# payload-schematic.net
KiCad netlist of a schematic drawn in EAGLE
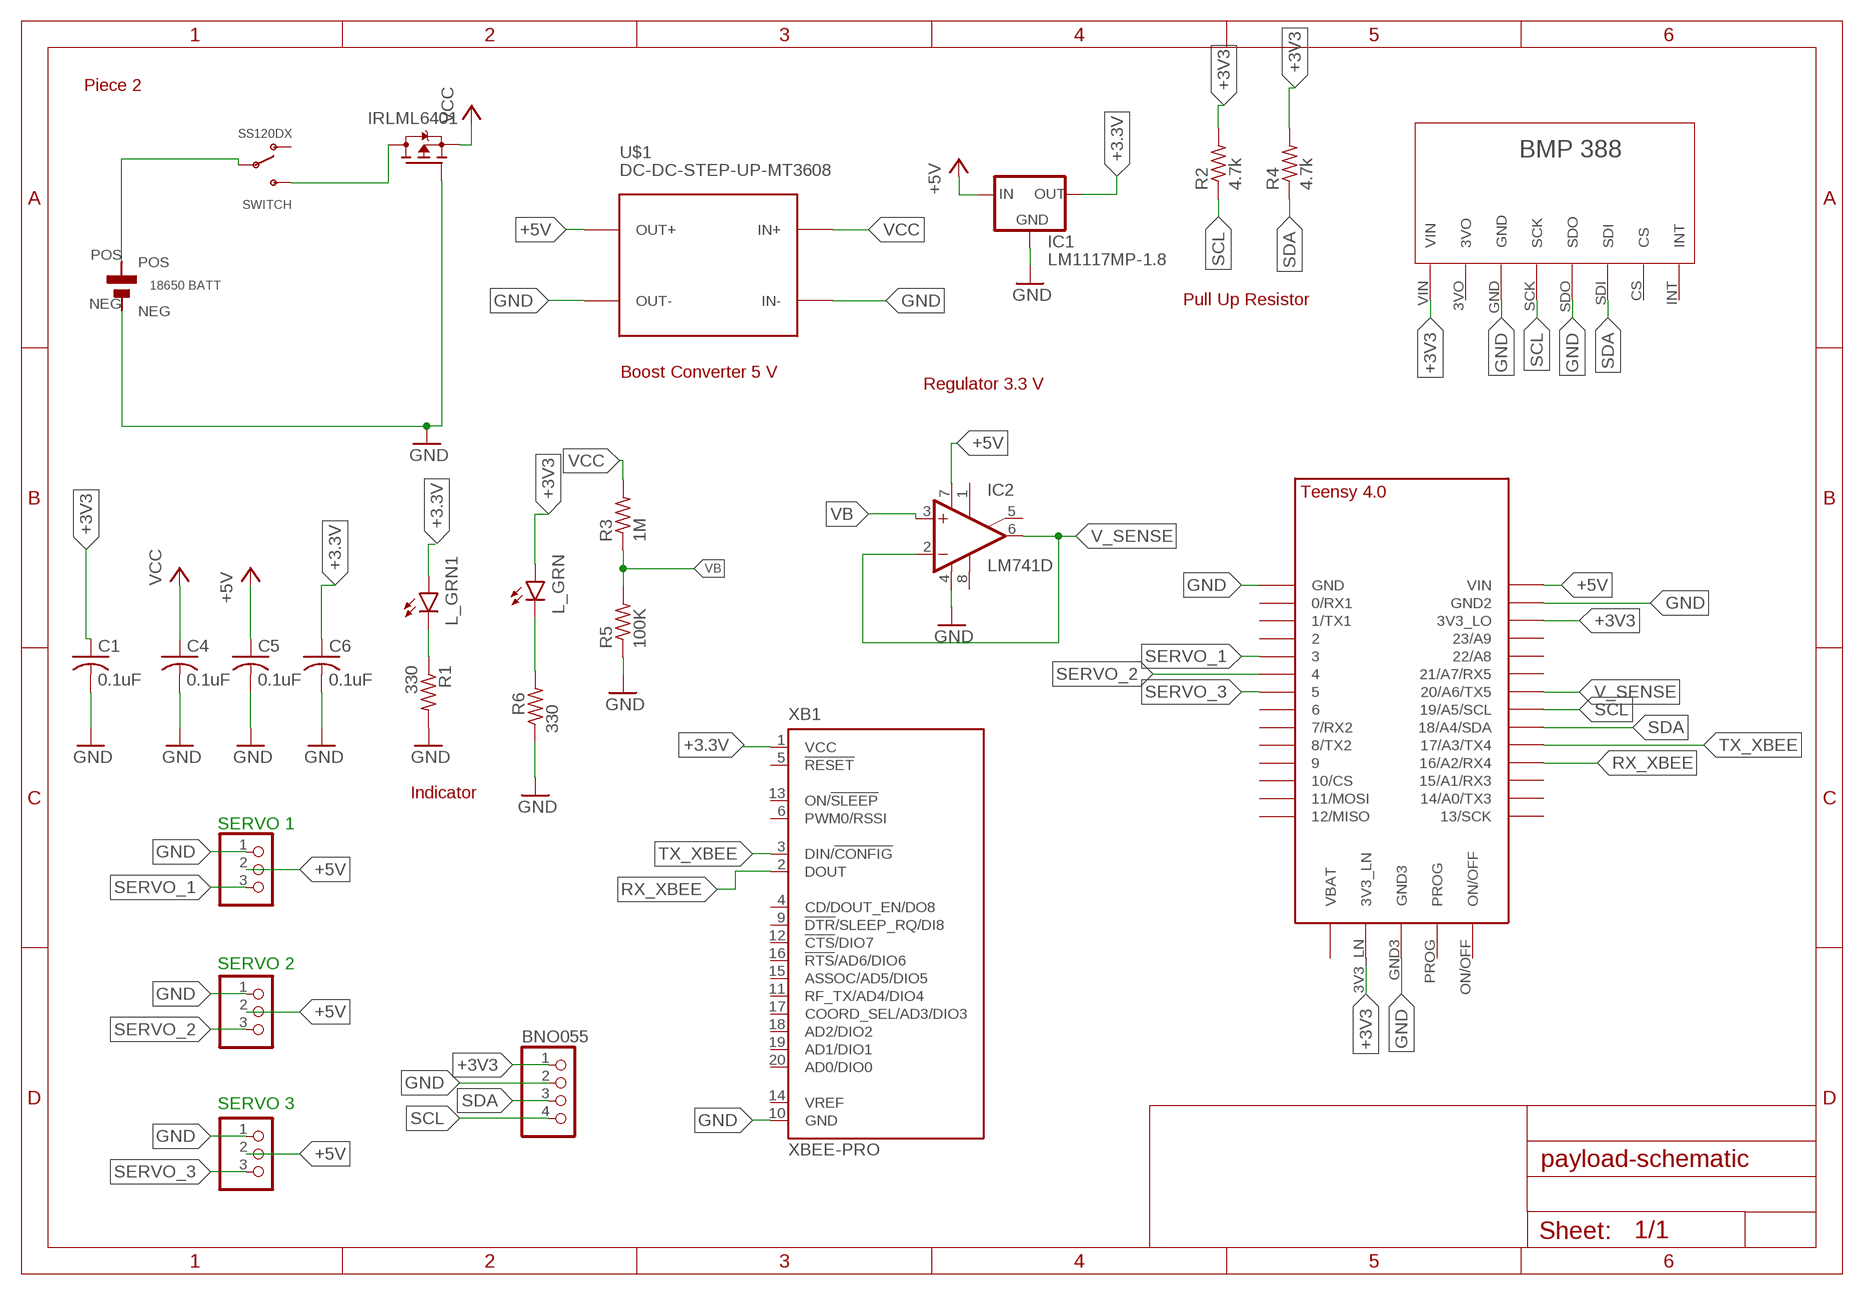
[diagram p0: schematic, sheet 1]

(export (version "E")
  (design (tool "Eeschema 10.0.6"))
  (components
    (comp (ref "BNO055")
      (value "PINHD-1X4")
      (footprint "eagle-import:1X04")
      (libsource (lib "eagle-import") (part "PINHD-1X4"))
    )
    (comp (ref "C1")
      (value "0.1uF")
      (footprint "eagle-import:C0805")
      (libsource (lib "eagle-import") (part "C-USC0805"))
    )
    (comp (ref "C4")
      (value "0.1uF")
      (footprint "eagle-import:C0805")
      (libsource (lib "eagle-import") (part "C-USC0805"))
    )
    (comp (ref "C5")
      (value "0.1uF")
      (footprint "eagle-import:C0805")
      (libsource (lib "eagle-import") (part "C-USC0805"))
    )
    (comp (ref "C6")
      (value "0.1uF")
      (footprint "eagle-import:C0805")
      (libsource (lib "eagle-import") (part "C-USC0805"))
    )
    (comp (ref "IC1")
      (value "LM1117MP-1.8")
      (footprint "eagle-import:SOT223")
      (fields (field (name "MF") "Texas Instruments"))
      (libsource (lib "eagle-import") (part "LM1117?-MP1.8"))
    )
    (comp (ref "IC2")
      (value "LM741D")
      (footprint "eagle-import:SO08")
      (libsource (lib "eagle-import") (part "741DLM"))
    )
    (comp (ref "IRLML6401")
      (value "MOSFET-PWIDE")
      (footprint "eagle-import:SOT23-WIDE")
      (libsource (lib "eagle-import") (part "MOSFET-PWIDE"))
    )
    (comp (ref "L_GRN")
      (value "LED1206")
      (footprint "eagle-import:LED-1206")
      (libsource (lib "eagle-import") (part "LED1206"))
    )
    (comp (ref "L_GRN1")
      (value "LED1206")
      (footprint "eagle-import:LED-1206")
      (libsource (lib "eagle-import") (part "LED1206"))
    )
    (comp (ref "R1")
      (value "330")
      (footprint "eagle-import:M0805")
      (libsource (lib "eagle-import") (part "R-US_M0805"))
    )
    (comp (ref "R2")
      (value "4.7k")
      (footprint "eagle-import:M0805")
      (libsource (lib "eagle-import") (part "R-US_M0805"))
    )
    (comp (ref "R3")
      (value "1M")
      (footprint "eagle-import:M1206")
      (libsource (lib "eagle-import") (part "R-US_M1206"))
    )
    (comp (ref "R4")
      (value "4.7k")
      (footprint "eagle-import:M0805")
      (libsource (lib "eagle-import") (part "R-US_M0805"))
    )
    (comp (ref "R5")
      (value "100K")
      (footprint "eagle-import:M1206")
      (libsource (lib "eagle-import") (part "R-US_M1206"))
    )
    (comp (ref "R6")
      (value "330")
      (footprint "eagle-import:M0805")
      (libsource (lib "eagle-import") (part "R-US_M0805"))
    )
    (comp (ref "SERVO1")
      (value "PINHD-1X3")
      (footprint "eagle-import:1X03")
      (libsource (lib "eagle-import") (part "PINHD-1X3"))
    )
    (comp (ref "SERVO2")
      (value "PINHD-1X3")
      (footprint "eagle-import:1X03")
      (libsource (lib "eagle-import") (part "PINHD-1X3"))
    )
    (comp (ref "SERVO3")
      (value "PINHD-1X3")
      (footprint "eagle-import:1X03")
      (libsource (lib "eagle-import") (part "PINHD-1X3"))
    )
    (comp (ref "SWITCH")
      (value "SS120DX")
      (footprint "eagle-import:SS12D0X")
      (libsource (lib "eagle-import") (part "SS120DX"))
    )
    (comp (ref "U$1")
      (value "DC-DC-STEP-UP-MT3608")
      (footprint "eagle-import:DC-DC-STEP-UP-MT3608")
      (libsource (lib "eagle-import") (part "DC-DC-STEP-UP-MT3608"))
    )
    (comp (ref "U$3")
      (value "BMP388")
      (footprint "eagle-import:BMP388")
      (libsource (lib "eagle-import") (part "BMP388"))
    )
    (comp (ref "U$4")
      (value "18650")
      (footprint "eagle-import:18650")
      (libsource (lib "eagle-import") (part "18650"))
    )
    (comp (ref "U$6")
      (value "TEENSY_4.0")
      (footprint "eagle-import:TEENSY_4.0")
      (libsource (lib "eagle-import") (part "TEENSY_4.0"))
    )
    (comp (ref "XB1")
      (value "XBEE-PRO")
      (footprint "eagle-import:XBEE-PRO")
      (fields (field (name "MPN") "XBP24-AWI-001"))
      (libsource (lib "eagle-import") (part "XBEE-PRO"))
    )
  )
  (nets
    (net (code "1") (name "+3.3V") (class "Default")
      (node (ref "C6") (pin "1") (pinfunction "1_1") (pintype "passive"))
      (node (ref "IC1") (pin "2") (pinfunction "OUT_2") (pintype "passive"))
      (node (ref "IC1") (pin "4") (pinfunction "OUT_4") (pintype "passive"))
      (node (ref "L_GRN1") (pin "A") (pinfunction "A_A") (pintype "passive"))
      (node (ref "XB1") (pin "1") (pinfunction "VCC_1") (pintype "power_in"))
    )
    (net (code "2") (name "+3V3") (class "Default")
      (node (ref "BNO055") (pin "1") (pinfunction "1_1") (pintype "passive"))
      (node (ref "C1") (pin "1") (pinfunction "1_1") (pintype "passive"))
      (node (ref "L_GRN") (pin "A") (pinfunction "A_A") (pintype "passive"))
      (node (ref "R2") (pin "2") (pinfunction "2_2") (pintype "passive"))
      (node (ref "R4") (pin "2") (pinfunction "2_2") (pintype "passive"))
      (node (ref "U$3") (pin "VIN") (pinfunction "VIN_VIN") (pintype "bidirectional"))
      (node (ref "U$6") (pin "3V3_LN") (pinfunction "3V3_LN_3V3_LN") (pintype "bidirectional"))
      (node (ref "U$6") (pin "3V3_LO") (pinfunction "3V3_LO_3V3_LO") (pintype "bidirectional"))
    )
    (net (code "3") (name "+5V") (class "Default")
      (node (ref "C5") (pin "1") (pinfunction "1_1") (pintype "passive"))
      (node (ref "IC1") (pin "3") (pinfunction "IN_3") (pintype "input"))
      (node (ref "IC2") (pin "7") (pinfunction "V+_7") (pintype "power_in"))
      (node (ref "SERVO1") (pin "2") (pinfunction "2_2") (pintype "passive"))
      (node (ref "SERVO2") (pin "2") (pinfunction "2_2") (pintype "passive"))
      (node (ref "SERVO3") (pin "2") (pinfunction "2_2") (pintype "passive"))
      (node (ref "U$1") (pin "OUT+") (pinfunction "OUT+_OUT+") (pintype "bidirectional"))
      (node (ref "U$6") (pin "VIN") (pinfunction "VIN_VIN") (pintype "bidirectional"))
    )
    (net (code "4") (name "GND") (class "Default")
      (node (ref "BNO055") (pin "2") (pinfunction "2_2") (pintype "passive"))
      (node (ref "C1") (pin "2") (pinfunction "2_2") (pintype "passive"))
      (node (ref "C4") (pin "2") (pinfunction "2_2") (pintype "passive"))
      (node (ref "C5") (pin "2") (pinfunction "2_2") (pintype "passive"))
      (node (ref "C6") (pin "2") (pinfunction "2_2") (pintype "passive"))
      (node (ref "IC1") (pin "1") (pinfunction "GND_1") (pintype "input"))
      (node (ref "IC2") (pin "4") (pinfunction "V-_4") (pintype "power_in"))
      (node (ref "IRLML6401") (pin "1") (pinfunction "G_1") (pintype "passive"))
      (node (ref "R1") (pin "2") (pinfunction "2_2") (pintype "passive"))
      (node (ref "R5") (pin "1") (pinfunction "1_1") (pintype "passive"))
      (node (ref "R6") (pin "1") (pinfunction "1_1") (pintype "passive"))
      (node (ref "SERVO1") (pin "1") (pinfunction "1_1") (pintype "passive"))
      (node (ref "SERVO2") (pin "1") (pinfunction "1_1") (pintype "passive"))
      (node (ref "SERVO3") (pin "1") (pinfunction "1_1") (pintype "passive"))
      (node (ref "U$1") (pin "IN-") (pinfunction "IN-_IN-") (pintype "bidirectional"))
      (node (ref "U$1") (pin "OUT-") (pinfunction "OUT-_OUT-") (pintype "bidirectional"))
      (node (ref "U$3") (pin "GND") (pinfunction "GND_GND") (pintype "bidirectional"))
      (node (ref "U$3") (pin "SDO") (pinfunction "SDO_SDO") (pintype "bidirectional"))
      (node (ref "U$4") (pin "NEG") (pinfunction "NEG_NEG") (pintype "bidirectional"))
      (node (ref "U$6") (pin "GND") (pinfunction "GND_GND") (pintype "bidirectional"))
      (node (ref "U$6") (pin "GND2") (pinfunction "GND2_GND2") (pintype "bidirectional"))
      (node (ref "U$6") (pin "GND3") (pinfunction "GND3_GND3") (pintype "bidirectional"))
      (node (ref "XB1") (pin "10") (pinfunction "GND_10") (pintype "power_in"))
    )
    (net (code "5") (name "Net-(IRLML6401-D)") (class "Default")
      (node (ref "IRLML6401") (pin "3") (pinfunction "D_3") (pintype "passive"))
      (node (ref "SWITCH") (pin "3") (pinfunction "3_3") (pintype "passive"))
    )
    (net (code "6") (name "Net-(L_GRN-PadC)") (class "Default")
      (node (ref "L_GRN") (pin "C") (pinfunction "C_C") (pintype "passive"))
      (node (ref "R6") (pin "2") (pinfunction "2_2") (pintype "passive"))
    )
    (net (code "7") (name "Net-(L_GRN1-PadC)") (class "Default")
      (node (ref "L_GRN1") (pin "C") (pinfunction "C_C") (pintype "passive"))
      (node (ref "R1") (pin "1") (pinfunction "1_1") (pintype "passive"))
    )
    (net (code "8") (name "Net-(SWITCH-Pad2)") (class "Default")
      (node (ref "SWITCH") (pin "2") (pinfunction "2_2") (pintype "passive"))
      (node (ref "U$4") (pin "POS") (pinfunction "POS_POS") (pintype "bidirectional"))
    )
    (net (code "9") (name "RX_XBEE") (class "Default")
      (node (ref "U$6") (pin "16/A2") (pinfunction "16/A2/RX4_16/A2") (pintype "bidirectional"))
      (node (ref "XB1") (pin "2") (pinfunction "DOUT_2") (pintype "output"))
    )
    (net (code "10") (name "SCL") (class "Default")
      (node (ref "BNO055") (pin "4") (pinfunction "4_4") (pintype "passive"))
      (node (ref "R2") (pin "1") (pinfunction "1_1") (pintype "passive"))
      (node (ref "U$3") (pin "SCK") (pinfunction "SCK_SCK") (pintype "bidirectional"))
      (node (ref "U$6") (pin "19/A5/SCL") (pinfunction "19/A5/SCL_19/A5/SCL") (pintype "bidirectional"))
    )
    (net (code "11") (name "SDA") (class "Default")
      (node (ref "BNO055") (pin "3") (pinfunction "3_3") (pintype "passive"))
      (node (ref "R4") (pin "1") (pinfunction "1_1") (pintype "passive"))
      (node (ref "U$3") (pin "SDI") (pinfunction "SDI_SDI") (pintype "bidirectional"))
      (node (ref "U$6") (pin "18/A4/SDA") (pinfunction "18/A4/SDA_18/A4/SDA") (pintype "bidirectional"))
    )
    (net (code "12") (name "SERVO_1") (class "Default")
      (node (ref "SERVO1") (pin "3") (pinfunction "3_3") (pintype "passive"))
      (node (ref "U$6") (pin "3/CANTX") (pinfunction "3_3/CANTX") (pintype "bidirectional"))
    )
    (net (code "13") (name "SERVO_2") (class "Default")
      (node (ref "SERVO2") (pin "3") (pinfunction "3_3") (pintype "passive"))
      (node (ref "U$6") (pin "4/CANRX") (pinfunction "4_4/CANRX") (pintype "bidirectional"))
    )
    (net (code "14") (name "SERVO_3") (class "Default")
      (node (ref "SERVO3") (pin "3") (pinfunction "3_3") (pintype "passive"))
      (node (ref "U$6") (pin "5") (pinfunction "5_5") (pintype "bidirectional"))
    )
    (net (code "15") (name "TX_XBEE") (class "Default")
      (node (ref "U$6") (pin "17/A3") (pinfunction "17/A3/TX4_17/A3") (pintype "bidirectional"))
      (node (ref "XB1") (pin "3") (pinfunction "DIN/~{CONFIG}_3") (pintype "input"))
    )
    (net (code "16") (name "VB") (class "Default")
      (node (ref "IC2") (pin "3") (pinfunction "+IN_3") (pintype "input"))
      (node (ref "R3") (pin "1") (pinfunction "1_1") (pintype "passive"))
      (node (ref "R5") (pin "2") (pinfunction "2_2") (pintype "passive"))
    )
    (net (code "17") (name "VCC") (class "Default")
      (node (ref "C4") (pin "1") (pinfunction "1_1") (pintype "passive"))
      (node (ref "IRLML6401") (pin "2") (pinfunction "S_2") (pintype "passive"))
      (node (ref "R3") (pin "2") (pinfunction "2_2") (pintype "passive"))
      (node (ref "U$1") (pin "IN+") (pinfunction "IN+_IN+") (pintype "bidirectional"))
    )
    (net (code "18") (name "V_SENSE") (class "Default")
      (node (ref "IC2") (pin "2") (pinfunction "-IN_2") (pintype "input"))
      (node (ref "IC2") (pin "6") (pinfunction "OUT_6") (pintype "output"))
      (node (ref "U$6") (pin "20/A6") (pinfunction "20/A6/TX5_20/A6") (pintype "bidirectional"))
    )
    (net (code "19") (name "unconnected-(IC2-ON1-Pad1)") (class "Default")
      (node (ref "IC2") (pin "1") (pinfunction "ON1_1") (pintype "passive"))
    )
    (net (code "20") (name "unconnected-(IC2-ON2-Pad5)") (class "Default")
      (node (ref "IC2") (pin "5") (pinfunction "ON2_5") (pintype "passive"))
    )
    (net (code "21") (name "unconnected-(IC2-OPT-Pad8)") (class "Default")
      (node (ref "IC2") (pin "8") (pinfunction "OPT_8") (pintype "passive"))
    )
    (net (code "22") (name "unconnected-(SWITCH-Pad1)") (class "Default")
      (node (ref "SWITCH") (pin "1") (pinfunction "1_1") (pintype "passive"))
    )
    (net (code "23") (name "unconnected-(U$3-Pad3VO)") (class "Default")
      (node (ref "U$3") (pin "3VO") (pinfunction "3VO_3VO") (pintype "bidirectional"))
    )
    (net (code "24") (name "unconnected-(U$3-PadCS)") (class "Default")
      (node (ref "U$3") (pin "CS") (pinfunction "CS_CS") (pintype "bidirectional"))
    )
    (net (code "25") (name "unconnected-(U$3-PadINT)") (class "Default")
      (node (ref "U$3") (pin "INT") (pinfunction "INT_INT") (pintype "bidirectional"))
    )
    (net (code "26") (name "unconnected-(U$6-0{slash}RX1-Pad0{slash}RX)") (class "Default")
      (node (ref "U$6") (pin "0/RX") (pinfunction "0/RX1_0/RX") (pintype "bidirectional"))
    )
    (net (code "27") (name "unconnected-(U$6-1{slash}TX1-Pad1{slash}TX)") (class "Default")
      (node (ref "U$6") (pin "1/TX") (pinfunction "1/TX1_1/TX") (pintype "bidirectional"))
    )
    (net (code "28") (name "unconnected-(U$6-7{slash}RX2-Pad7)") (class "Default")
      (node (ref "U$6") (pin "7") (pinfunction "7/RX2_7") (pintype "bidirectional"))
    )
    (net (code "29") (name "unconnected-(U$6-8{slash}TX2-Pad8)") (class "Default")
      (node (ref "U$6") (pin "8") (pinfunction "8/TX2_8") (pintype "bidirectional"))
    )
    (net (code "30") (name "unconnected-(U$6-9-Pad9{slash}CS)") (class "Default")
      (node (ref "U$6") (pin "9/CS") (pinfunction "9_9/CS") (pintype "bidirectional"))
    )
    (net (code "31") (name "unconnected-(U$6-14{slash}A0{slash}TX3-Pad14{slash}A0)") (class "Default")
      (node (ref "U$6") (pin "14/A0") (pinfunction "14/A0/TX3_14/A0") (pintype "bidirectional"))
    )
    (net (code "32") (name "unconnected-(U$6-15{slash}A1{slash}RX3-Pad15{slash}A1)") (class "Default")
      (node (ref "U$6") (pin "15/A1") (pinfunction "15/A1/RX3_15/A1") (pintype "bidirectional"))
    )
    (net (code "33") (name "unconnected-(U$6-21{slash}A7{slash}RX5-Pad21{slash}A7)") (class "Default")
      (node (ref "U$6") (pin "21/A7") (pinfunction "21/A7/RX5_21/A7") (pintype "bidirectional"))
    )
    (net (code "34") (name "unconnected-(U$6-Pad2)") (class "Default")
      (node (ref "U$6") (pin "2") (pinfunction "2_2") (pintype "bidirectional"))
    )
    (net (code "35") (name "unconnected-(U$6-Pad6)") (class "Default")
      (node (ref "U$6") (pin "6") (pinfunction "6_6") (pintype "bidirectional"))
    )
    (net (code "36") (name "unconnected-(U$6-Pad10{slash}CS)") (class "Default")
      (node (ref "U$6") (pin "10/CS") (pinfunction "10/CS_10/CS") (pintype "bidirectional"))
    )
    (net (code "37") (name "unconnected-(U$6-Pad11{slash}MOSI)") (class "Default")
      (node (ref "U$6") (pin "11/MOSI") (pinfunction "11/MOSI_11/MOSI") (pintype "bidirectional"))
    )
    (net (code "38") (name "unconnected-(U$6-Pad12{slash}MISO)") (class "Default")
      (node (ref "U$6") (pin "12/MISO") (pinfunction "12/MISO_12/MISO") (pintype "bidirectional"))
    )
    (net (code "39") (name "unconnected-(U$6-Pad13{slash}SCK)") (class "Default")
      (node (ref "U$6") (pin "13/SCK") (pinfunction "13/SCK_13/SCK") (pintype "bidirectional"))
    )
    (net (code "40") (name "unconnected-(U$6-Pad22{slash}A8)") (class "Default")
      (node (ref "U$6") (pin "22/A8") (pinfunction "22/A8_22/A8") (pintype "bidirectional"))
    )
    (net (code "41") (name "unconnected-(U$6-Pad23{slash}A9)") (class "Default")
      (node (ref "U$6") (pin "23/A9") (pinfunction "23/A9_23/A9") (pintype "bidirectional"))
    )
    (net (code "42") (name "unconnected-(U$6-PadON{slash}OFF)") (class "Default")
      (node (ref "U$6") (pin "ON/OFF") (pinfunction "ON/OFF_ON/OFF") (pintype "bidirectional"))
    )
    (net (code "43") (name "unconnected-(U$6-PadPROG)") (class "Default")
      (node (ref "U$6") (pin "PROG") (pinfunction "PROG_PROG") (pintype "bidirectional"))
    )
    (net (code "44") (name "unconnected-(U$6-VBAT-PadVBAT\\)") (class "Default")
      (node (ref "U$6") (pin "VBAT\\") (pinfunction "VBAT_VBAT\\") (pintype "bidirectional"))
    )
    (net (code "45") (name "unconnected-(XB1-AD0{slash}DIO0-Pad20)") (class "Default")
      (node (ref "XB1") (pin "20") (pinfunction "AD0/DIO0_20") (pintype "bidirectional"))
    )
    (net (code "46") (name "unconnected-(XB1-AD1{slash}DIO1-Pad19)") (class "Default")
      (node (ref "XB1") (pin "19") (pinfunction "AD1/DIO1_19") (pintype "bidirectional"))
    )
    (net (code "47") (name "unconnected-(XB1-AD2{slash}DIO2-Pad18)") (class "Default")
      (node (ref "XB1") (pin "18") (pinfunction "AD2/DIO2_18") (pintype "bidirectional"))
    )
    (net (code "48") (name "unconnected-(XB1-ASSOC{slash}AD5{slash}DIO5-Pad15)") (class "Default")
      (node (ref "XB1") (pin "15") (pinfunction "ASSOC/AD5/DIO5_15") (pintype "bidirectional"))
    )
    (net (code "49") (name "unconnected-(XB1-CD{slash}DOUT_EN{slash}DO8-Pad4)") (class "Default")
      (node (ref "XB1") (pin "4") (pinfunction "CD/DOUT_EN/DO8_4") (pintype "output"))
    )
    (net (code "50") (name "unconnected-(XB1-COORD_SEL{slash}AD3{slash}DIO3-Pad17)") (class "Default")
      (node (ref "XB1") (pin "17") (pinfunction "COORD_SEL/AD3/DIO3_17") (pintype "bidirectional"))
    )
    (net (code "51") (name "unconnected-(XB1-ON{slash}~{SLEEP}-Pad13)") (class "Default")
      (node (ref "XB1") (pin "13") (pinfunction "ON/~{SLEEP}_13") (pintype "output"))
    )
    (net (code "52") (name "unconnected-(XB1-PWM0{slash}RSSI-Pad6)") (class "Default")
      (node (ref "XB1") (pin "6") (pinfunction "PWM0/RSSI_6") (pintype "output"))
    )
    (net (code "53") (name "unconnected-(XB1-RF_TX{slash}AD4{slash}DIO4-Pad11)") (class "Default")
      (node (ref "XB1") (pin "11") (pinfunction "RF_TX/AD4/DIO4_11") (pintype "bidirectional"))
    )
    (net (code "54") (name "unconnected-(XB1-VREF-Pad14)") (class "Default")
      (node (ref "XB1") (pin "14") (pinfunction "VREF_14") (pintype "input"))
    )
    (net (code "55") (name "unconnected-(XB1-~{CTS}{slash}DIO7-Pad12)") (class "Default")
      (node (ref "XB1") (pin "12") (pinfunction "~{CTS}/DIO7_12") (pintype "bidirectional"))
    )
    (net (code "56") (name "unconnected-(XB1-~{DTR}{slash}SLEEP_RQ{slash}DI8-Pad9)") (class "Default")
      (node (ref "XB1") (pin "9") (pinfunction "~{DTR}/SLEEP_RQ/DI8_9") (pintype "bidirectional"))
    )
    (net (code "57") (name "unconnected-(XB1-~{RESET}-Pad5)") (class "Default")
      (node (ref "XB1") (pin "5") (pinfunction "~{RESET}_5") (pintype "input"))
    )
    (net (code "58") (name "unconnected-(XB1-~{RTS}{slash}AD6{slash}DIO6-Pad16)") (class "Default")
      (node (ref "XB1") (pin "16") (pinfunction "~{RTS}/AD6/DIO6_16") (pintype "bidirectional"))
    )
  )
)
